# USB3_Replication.net
KiCad netlist of a schematic drawn in Altium Designer
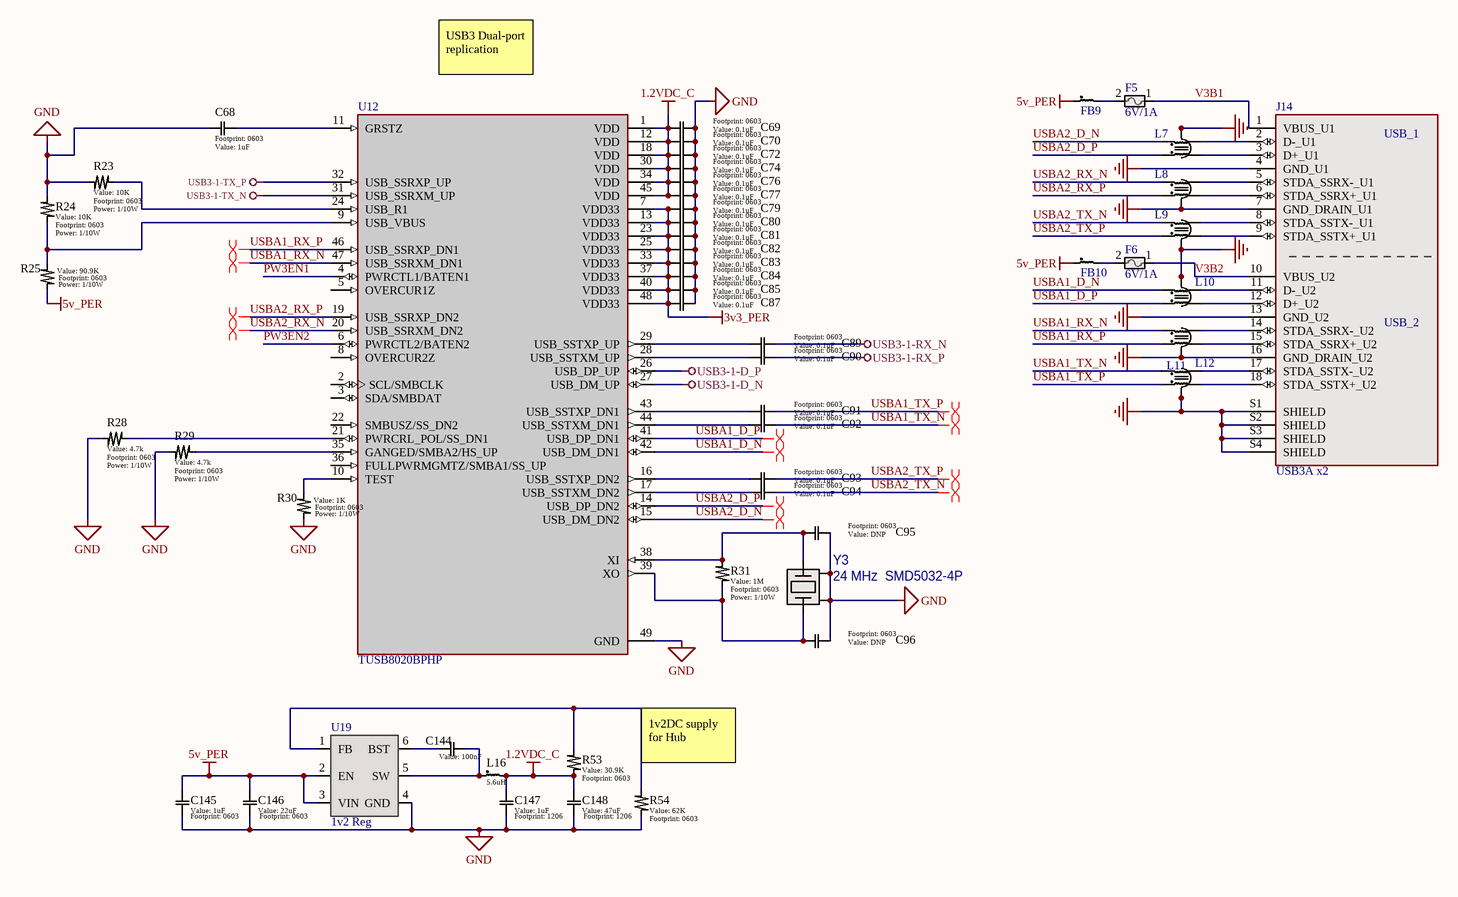
[diagram p0: USB3_Replication.SchDoc]

(export (version "E")
  (design (tool "Eeschema 10.0.6"))
  (components
    (comp (ref "C68")
      (value "1uF")
      (footprint "0603")
      (fields
        (field (name "VOLTAGE") ">10V")
        (field (name "TOLERANCE") "10%")
        (field (name "Comment") "Generic Capacitor")
      )
      (libsource (lib "Capacitors") (part "Generic Capacitor"))
    )
    (comp (ref "C69")
      (value "0.1uF")
      (footprint "0603")
      (fields
        (field (name "VOLTAGE") "10V")
        (field (name "TOLERANCE") "10%")
        (field (name "Comment") "Generic Capacitor")
      )
      (libsource (lib "Capacitors") (part "Generic Capacitor"))
    )
    (comp (ref "C70")
      (value "0.1uF")
      (footprint "0603")
      (fields
        (field (name "VOLTAGE") "10V")
        (field (name "TOLERANCE") "10%")
        (field (name "Comment") "Generic Capacitor")
      )
      (libsource (lib "Capacitors") (part "Generic Capacitor"))
    )
    (comp (ref "C72")
      (value "0.1uF")
      (footprint "0603")
      (fields
        (field (name "VOLTAGE") "10V")
        (field (name "TOLERANCE") "10%")
        (field (name "Comment") "Generic Capacitor")
      )
      (libsource (lib "Capacitors") (part "Generic Capacitor"))
    )
    (comp (ref "C74")
      (value "0.1uF")
      (footprint "0603")
      (fields
        (field (name "VOLTAGE") "10V")
        (field (name "TOLERANCE") "10%")
        (field (name "Comment") "Generic Capacitor")
      )
      (libsource (lib "Capacitors") (part "Generic Capacitor"))
    )
    (comp (ref "C76")
      (value "0.1uF")
      (footprint "0603")
      (fields
        (field (name "VOLTAGE") "10V")
        (field (name "TOLERANCE") "10%")
        (field (name "Comment") "Generic Capacitor")
      )
      (libsource (lib "Capacitors") (part "Generic Capacitor"))
    )
    (comp (ref "C77")
      (value "0.1uF")
      (footprint "0603")
      (fields
        (field (name "VOLTAGE") "10V")
        (field (name "TOLERANCE") "10%")
        (field (name "Comment") "Generic Capacitor")
      )
      (libsource (lib "Capacitors") (part "Generic Capacitor"))
    )
    (comp (ref "C79")
      (value "0.1uF")
      (footprint "0603")
      (fields
        (field (name "VOLTAGE") "10V")
        (field (name "TOLERANCE") "10%")
        (field (name "Comment") "Generic Capacitor")
      )
      (libsource (lib "Capacitors") (part "Generic Capacitor"))
    )
    (comp (ref "C80")
      (value "0.1uF")
      (footprint "0603")
      (fields
        (field (name "VOLTAGE") "10V")
        (field (name "TOLERANCE") "10%")
        (field (name "Comment") "Generic Capacitor")
      )
      (libsource (lib "Capacitors") (part "Generic Capacitor"))
    )
    (comp (ref "C81")
      (value "0.1uF")
      (footprint "0603")
      (fields
        (field (name "VOLTAGE") "10V")
        (field (name "TOLERANCE") "10%")
        (field (name "Comment") "Generic Capacitor")
      )
      (libsource (lib "Capacitors") (part "Generic Capacitor"))
    )
    (comp (ref "C82")
      (value "0.1uF")
      (footprint "0603")
      (fields
        (field (name "VOLTAGE") "10V")
        (field (name "TOLERANCE") "10%")
        (field (name "Comment") "Generic Capacitor")
      )
      (libsource (lib "Capacitors") (part "Generic Capacitor"))
    )
    (comp (ref "C83")
      (value "0.1uF")
      (footprint "0603")
      (fields
        (field (name "VOLTAGE") "10V")
        (field (name "TOLERANCE") "10%")
        (field (name "Comment") "Generic Capacitor")
      )
      (libsource (lib "Capacitors") (part "Generic Capacitor"))
    )
    (comp (ref "C84")
      (value "0.1uF")
      (footprint "0603")
      (fields
        (field (name "VOLTAGE") "10V")
        (field (name "TOLERANCE") "10%")
        (field (name "Comment") "Generic Capacitor")
      )
      (libsource (lib "Capacitors") (part "Generic Capacitor"))
    )
    (comp (ref "C85")
      (value "0.1uF")
      (footprint "0603")
      (fields
        (field (name "VOLTAGE") "10V")
        (field (name "TOLERANCE") "10%")
        (field (name "Comment") "Generic Capacitor")
      )
      (libsource (lib "Capacitors") (part "Generic Capacitor"))
    )
    (comp (ref "C87")
      (value "0.1uF")
      (footprint "0603")
      (fields
        (field (name "VOLTAGE") "10V")
        (field (name "TOLERANCE") "10%")
        (field (name "Comment") "Generic Capacitor")
      )
      (libsource (lib "Capacitors") (part "Generic Capacitor"))
    )
    (comp (ref "C89")
      (value "0.1uF")
      (footprint "0603")
      (fields
        (field (name "VOLTAGE") "10V")
        (field (name "TOLERANCE") "10%")
        (field (name "Comment") "Generic Capacitor")
      )
      (libsource (lib "Capacitors") (part "Generic Capacitor"))
    )
    (comp (ref "C90")
      (value "0.1uF")
      (footprint "0603")
      (fields
        (field (name "VOLTAGE") "10V")
        (field (name "TOLERANCE") "10%")
        (field (name "Comment") "Generic Capacitor")
      )
      (libsource (lib "Capacitors") (part "Generic Capacitor"))
    )
    (comp (ref "C91")
      (value "0.1uF")
      (footprint "0603")
      (fields
        (field (name "VOLTAGE") "10V")
        (field (name "TOLERANCE") "10%")
        (field (name "Comment") "Generic Capacitor")
      )
      (libsource (lib "Capacitors") (part "Generic Capacitor"))
    )
    (comp (ref "C92")
      (value "0.1uF")
      (footprint "0603")
      (fields
        (field (name "VOLTAGE") "10V")
        (field (name "TOLERANCE") "10%")
        (field (name "Comment") "Generic Capacitor")
      )
      (libsource (lib "Capacitors") (part "Generic Capacitor"))
    )
    (comp (ref "C93")
      (value "0.1uF")
      (footprint "0603")
      (fields
        (field (name "VOLTAGE") "10V")
        (field (name "TOLERANCE") "10%")
        (field (name "Comment") "Generic Capacitor")
      )
      (libsource (lib "Capacitors") (part "Generic Capacitor"))
    )
    (comp (ref "C94")
      (value "0.1uF")
      (footprint "0603")
      (fields
        (field (name "VOLTAGE") "10V")
        (field (name "TOLERANCE") "10%")
        (field (name "Comment") "Generic Capacitor")
      )
      (libsource (lib "Capacitors") (part "Generic Capacitor"))
    )
    (comp (ref "C95")
      (value "DNP")
      (footprint "0603")
      (fields
        (field (name "VOLTAGE") ">10V")
        (field (name "TOLERANCE") "10%")
        (field (name "Comment") "Generic Capacitor")
      )
      (libsource (lib "Capacitors") (part "Generic Capacitor"))
    )
    (comp (ref "C96")
      (value "DNP")
      (footprint "0603")
      (fields
        (field (name "VOLTAGE") ">10V")
        (field (name "TOLERANCE") "10%")
        (field (name "Comment") "Generic Capacitor")
      )
      (libsource (lib "Capacitors") (part "Generic Capacitor"))
    )
    (comp (ref "C144")
      (value "100nF")
      (footprint "0603")
      (fields
        (field (name "VOLTAGE") ">10V")
        (field (name "TOLERANCE") "10%")
        (field (name "Comment") "Generic Capacitor")
      )
      (libsource (lib "Capacitors") (part "Generic Capacitor"))
    )
    (comp (ref "C145")
      (value "1uF")
      (footprint "0603")
      (fields
        (field (name "VOLTAGE") ">10V")
        (field (name "TOLERANCE") "10%")
        (field (name "Comment") "Generic Capacitor")
      )
      (libsource (lib "Capacitors") (part "Generic Capacitor"))
    )
    (comp (ref "C146")
      (value "22uF")
      (footprint "0603")
      (fields
        (field (name "VOLTAGE") ">10V")
        (field (name "TOLERANCE") "10%")
        (field (name "Comment") "Generic Capacitor")
      )
      (libsource (lib "Capacitors") (part "Generic Capacitor"))
    )
    (comp (ref "C147")
      (value "1uF")
      (footprint "1206")
      (fields
        (field (name "VOLTAGE") ">10V")
        (field (name "TOLERANCE") "10%")
        (field (name "Comment") "Generic Capacitor")
      )
      (libsource (lib "Capacitors") (part "Generic Capacitor"))
    )
    (comp (ref "C148")
      (value "47uF")
      (footprint "1206")
      (fields
        (field (name "VOLTAGE") ">10V")
        (field (name "TOLERANCE") "10%")
        (field (name "Comment") "Generic Capacitor")
      )
      (libsource (lib "Capacitors") (part "Generic Capacitor"))
    )
    (comp (ref "F5")
      (value "6V/1A")
      (footprint "0805")
      (description "Polymeric PTC Resettable Fuse 6V 1 A Ih Surface Mount 0805 (2012 Metric), Concave")
      (fields (field (name "MANUFACTURER") "Bel") (field (name "MANUFACTURER PART NUMBER") "0ZCK0100FF2E"))
      (libsource (lib "Regulators") (part "0ZCK0100FF2E"))
    )
    (comp (ref "F6")
      (value "6V/1A")
      (footprint "0805")
      (description "Polymeric PTC Resettable Fuse 6V 1 A Ih Surface Mount 0805 (2012 Metric), Concave")
      (fields (field (name "MANUFACTURER") "Bel") (field (name "MANUFACTURER PART NUMBER") "0ZCK0100FF2E"))
      (libsource (lib "Regulators") (part "0ZCK0100FF2E"))
    )
    (comp (ref "FB9")
      (value "0603 Ferrite")
      (footprint "0603")
      (description "120 Ohms @ 100 MHz 1 Signal Line Ferrite Bead 0603 (1608 Metric) 500mA 180mOhm")
      (fields
        (field (name "MANUFACTURER") "Pulse")
        (field (name "MANUFACTURER PART NUMBER") "PE-0603FB121ST")
      )
      (libsource (lib "Inductors") (part "PE-0603FB121ST"))
    )
    (comp (ref "FB10")
      (value "0603 Ferrite")
      (footprint "0603")
      (description "120 Ohms @ 100 MHz 1 Signal Line Ferrite Bead 0603 (1608 Metric) 500mA 180mOhm")
      (fields
        (field (name "MANUFACTURER") "Pulse")
        (field (name "MANUFACTURER PART NUMBER") "PE-0603FB121ST")
      )
      (libsource (lib "Inductors") (part "PE-0603FB121ST"))
    )
    (comp (ref "J14")
      (value "USB3A x2")
      (footprint "0484060003")
      (fields (field (name "MP") "0484060003") (field (name "MF") "Molex"))
      (libsource (lib "Connectors") (part "0484060003"))
    )
    (comp (ref "L7")
      (value "2CH CMC")
      (footprint "SMD-6-2CH")
      (description "35Ω@100MHz -40℃~+85℃ 4Ω 5V 2 100mA SMD Common Mode Filters ROHS")
      (libsource (lib "") (part "ICMEF112P350MFR_1"))
    )
    (comp (ref "L8")
      (value "2CH CMC")
      (footprint "SMD-6-2CH")
      (description "35Ω@100MHz -40℃~+85℃ 4Ω 5V 2 100mA SMD Common Mode Filters ROHS")
      (libsource (lib "Inductors") (part "ICMEF112P350MFR"))
    )
    (comp (ref "L9")
      (value "2CH CMC")
      (footprint "SMD-6-2CH")
      (description "35Ω@100MHz -40℃~+85℃ 4Ω 5V 2 100mA SMD Common Mode Filters ROHS")
      (libsource (lib "Inductors") (part "ICMEF112P350MFR"))
    )
    (comp (ref "L10")
      (value "2CH CMC")
      (footprint "SMD-6-2CH")
      (description "35Ω@100MHz -40℃~+85℃ 4Ω 5V 2 100mA SMD Common Mode Filters ROHS")
      (libsource (lib "") (part "ICMEF112P350MFR_1"))
    )
    (comp (ref "L11")
      (value "2CH CMC")
      (footprint "SMD-6-2CH")
      (description "35Ω@100MHz -40℃~+85℃ 4Ω 5V 2 100mA SMD Common Mode Filters ROHS")
      (libsource (lib "Inductors") (part "ICMEF112P350MFR"))
    )
    (comp (ref "L12")
      (value "2CH CMC")
      (footprint "SMD-6-2CH")
      (description "35Ω@100MHz -40℃~+85℃ 4Ω 5V 2 100mA SMD Common Mode Filters ROHS")
      (libsource (lib "Inductors") (part "ICMEF112P350MFR"))
    )
    (comp (ref "L16")
      (value "5.6uH")
      (footprint "TMPC0402HP")
      (description "2A 5.6uH ±20% SMD Power Inductor")
      (libsource (lib "Inductors") (part "TMPC0402HP-5R6MG-Z02"))
    )
    (comp (ref "R23")
      (value "10K")
      (footprint "0603")
      (fields
        (field (name "TOLERANCE") "1%")
        (field (name "POWER") "1/10W")
        (field (name "Comment") "Generic Resistor")
      )
      (libsource (lib "Resistors") (part "Generic Resistor"))
    )
    (comp (ref "R24")
      (value "10K")
      (footprint "0603")
      (fields
        (field (name "TOLERANCE") "1%")
        (field (name "POWER") "1/10W")
        (field (name "Comment") "Generic Resistor")
      )
      (libsource (lib "Resistors") (part "Generic Resistor"))
    )
    (comp (ref "R25")
      (value "90.9K")
      (footprint "0603")
      (fields
        (field (name "TOLERANCE") "1%")
        (field (name "POWER") "1/10W")
        (field (name "Comment") "Generic Resistor")
      )
      (libsource (lib "Resistors") (part "Generic Resistor"))
    )
    (comp (ref "R28")
      (value "4.7k")
      (footprint "0603")
      (fields
        (field (name "TOLERANCE") "1%")
        (field (name "POWER") "1/10W")
        (field (name "Comment") "Generic Resistor")
      )
      (libsource (lib "Resistors") (part "Generic Resistor"))
    )
    (comp (ref "R29")
      (value "4.7k")
      (footprint "0603")
      (fields
        (field (name "TOLERANCE") "1%")
        (field (name "POWER") "1/10W")
        (field (name "Comment") "Generic Resistor")
      )
      (libsource (lib "Resistors") (part "Generic Resistor"))
    )
    (comp (ref "R30")
      (value "1K")
      (footprint "0603")
      (fields
        (field (name "TOLERANCE") "1%")
        (field (name "POWER") "1/10W")
        (field (name "Comment") "Generic Resistor")
      )
      (libsource (lib "Resistors") (part "Generic Resistor"))
    )
    (comp (ref "R31")
      (value "1M")
      (footprint "0603")
      (fields
        (field (name "TOLERANCE") "1%")
        (field (name "POWER") "1/10W")
        (field (name "Comment") "Generic Resistor")
      )
      (libsource (lib "Resistors") (part "Generic Resistor"))
    )
    (comp (ref "R53")
      (value "30.9K")
      (footprint "0603")
      (fields
        (field (name "TOLERANCE") "1%")
        (field (name "POWER") "1/10W")
        (field (name "Comment") "Generic Resistor")
      )
      (libsource (lib "Resistors") (part "Generic Resistor"))
    )
    (comp (ref "R54")
      (value "62K")
      (footprint "0603")
      (fields
        (field (name "TOLERANCE") "1%")
        (field (name "POWER") "1/10W")
        (field (name "Comment") "Generic Resistor")
      )
      (libsource (lib "Resistors") (part "Generic Resistor"))
    )
    (comp (ref "U12")
      (value "TUSB8020BPHP")
      (footprint "HTQFP-48(7x7)")
      (description "USB Hub Controller USB 3.0")
      (libsource (lib "Misc ICs") (part "TUSB8020BPHP"))
    )
    (comp (ref "U19")
      (value "1v2 Reg")
      (footprint "TSOT-23-6")
      (description "Step-down type Adjustable 2A 1.2V~12V 3.8V~32V TSOT-23-6 DC-DC Converter")
      (libsource (lib "Regulators") (part "AP63201WU-7"))
    )
    (comp (ref "Y3")
      (value "24 MHz  SMD5032-4P")
      (footprint "ECS-240-18-30BQ-DS")
      (description "24 MHz ±30ppm Crystal 18pF 30 Ohms 4-SMD, No Lead")
      (libsource (lib "Gamber - Johnson LLC") (part "ECS-240-18-30BQ-DS"))
    )
  )
  (nets
    (net (code "1") (name "/PW3EN1") (class "Default")
      (node (ref "U12") (pin "4") (pinfunction "PWRCTL1/BATEN1_4") (pintype "bidirectional"))
    )
    (net (code "2") (name "/PW3EN2") (class "Default")
      (node (ref "U12") (pin "6") (pinfunction "PWRCTL2/BATEN2_6") (pintype "bidirectional"))
    )
    (net (code "3") (name "/USBA1_D_N") (class "Default")
      (node (ref "L10") (pin "2") (pinfunction "2_2") (pintype "passive"))
      (node (ref "U12") (pin "42") (pinfunction "USB_DM_DN1_42") (pintype "bidirectional"))
    )
    (net (code "4") (name "/USBA1_D_P") (class "Default")
      (node (ref "L10") (pin "1") (pinfunction "1_1") (pintype "passive"))
      (node (ref "U12") (pin "41") (pinfunction "USB_DP_DN1_41") (pintype "bidirectional"))
    )
    (net (code "5") (name "/USBA1_RX_N") (class "Default")
      (node (ref "L11") (pin "1") (pinfunction "1_1") (pintype "passive"))
      (node (ref "U12") (pin "47") (pinfunction "USB_SSRXM_DN1_47") (pintype "input"))
    )
    (net (code "6") (name "/USBA1_RX_P") (class "Default")
      (node (ref "L11") (pin "2") (pinfunction "2_2") (pintype "passive"))
      (node (ref "U12") (pin "46") (pinfunction "USB_SSRXP_DN1_46") (pintype "input"))
    )
    (net (code "7") (name "/USBA1_TX_N") (class "Default")
      (node (ref "C92") (pin "1") (pinfunction "1_1") (pintype "passive"))
      (node (ref "L12") (pin "1") (pinfunction "1_1") (pintype "passive"))
    )
    (net (code "8") (name "/USBA1_TX_P") (class "Default")
      (node (ref "C91") (pin "1") (pinfunction "1_1") (pintype "passive"))
      (node (ref "L12") (pin "2") (pinfunction "2_2") (pintype "passive"))
    )
    (net (code "9") (name "/USBA2_D_N") (class "Default")
      (node (ref "L7") (pin "2") (pinfunction "2_2") (pintype "passive"))
      (node (ref "U12") (pin "15") (pinfunction "USB_DM_DN2_15") (pintype "bidirectional"))
    )
    (net (code "10") (name "/USBA2_D_P") (class "Default")
      (node (ref "L7") (pin "1") (pinfunction "1_1") (pintype "passive"))
      (node (ref "U12") (pin "14") (pinfunction "USB_DP_DN2_14") (pintype "bidirectional"))
    )
    (net (code "11") (name "/USBA2_RX_N") (class "Default")
      (node (ref "L8") (pin "1") (pinfunction "1_1") (pintype "passive"))
      (node (ref "U12") (pin "20") (pinfunction "USB_SSRXM_DN2_20") (pintype "input"))
    )
    (net (code "12") (name "/USBA2_RX_P") (class "Default")
      (node (ref "L8") (pin "2") (pinfunction "2_2") (pintype "passive"))
      (node (ref "U12") (pin "19") (pinfunction "USB_SSRXP_DN2_19") (pintype "input"))
    )
    (net (code "13") (name "/USBA2_TX_N") (class "Default")
      (node (ref "C94") (pin "1") (pinfunction "1_1") (pintype "passive"))
      (node (ref "L9") (pin "1") (pinfunction "1_1") (pintype "passive"))
    )
    (net (code "14") (name "/USBA2_TX_P") (class "Default")
      (node (ref "C93") (pin "1") (pinfunction "1_1") (pintype "passive"))
      (node (ref "L9") (pin "2") (pinfunction "2_2") (pintype "passive"))
    )
    (net (code "15") (name "/V3B1") (class "Default")
      (node (ref "F5") (pin "1") (pinfunction "1_1") (pintype "passive"))
      (node (ref "J14") (pin "1") (pinfunction "VBUS_U1_1") (pintype "power_in"))
    )
    (net (code "16") (name "/V3B2") (class "Default")
      (node (ref "F6") (pin "1") (pinfunction "1_1") (pintype "passive"))
      (node (ref "J14") (pin "10") (pinfunction "VBUS_U2_10") (pintype "power_in"))
    )
    (net (code "17") (name "1.2VDC_C") (class "Default")
      (node (ref "C147") (pin "1") (pinfunction "1_1") (pintype "passive"))
      (node (ref "C148") (pin "1") (pinfunction "1_1") (pintype "passive"))
      (node (ref "C69") (pin "2") (pinfunction "2_2") (pintype "passive"))
      (node (ref "C70") (pin "2") (pinfunction "2_2") (pintype "passive"))
      (node (ref "C72") (pin "2") (pinfunction "2_2") (pintype "passive"))
      (node (ref "C74") (pin "2") (pinfunction "2_2") (pintype "passive"))
      (node (ref "C76") (pin "2") (pinfunction "2_2") (pintype "passive"))
      (node (ref "C77") (pin "2") (pinfunction "2_2") (pintype "passive"))
      (node (ref "L16") (pin "2") (pinfunction "2_2") (pintype "passive"))
      (node (ref "R53") (pin "1") (pinfunction "1_1") (pintype "passive"))
      (node (ref "U12") (pin "1") (pinfunction "VDD_1") (pintype "power_in"))
      (node (ref "U12") (pin "12") (pinfunction "VDD_12") (pintype "power_in"))
      (node (ref "U12") (pin "18") (pinfunction "VDD_18") (pintype "power_in"))
      (node (ref "U12") (pin "30") (pinfunction "VDD_30") (pintype "power_in"))
      (node (ref "U12") (pin "34") (pinfunction "VDD_34") (pintype "power_in"))
      (node (ref "U12") (pin "45") (pinfunction "VDD_45") (pintype "power_in"))
    )
    (net (code "18") (name "3v3_PER") (class "Default")
      (node (ref "C79") (pin "2") (pinfunction "2_2") (pintype "passive"))
      (node (ref "C80") (pin "2") (pinfunction "2_2") (pintype "passive"))
      (node (ref "C81") (pin "2") (pinfunction "2_2") (pintype "passive"))
      (node (ref "C82") (pin "2") (pinfunction "2_2") (pintype "passive"))
      (node (ref "C83") (pin "2") (pinfunction "2_2") (pintype "passive"))
      (node (ref "C84") (pin "2") (pinfunction "2_2") (pintype "passive"))
      (node (ref "C85") (pin "2") (pinfunction "2_2") (pintype "passive"))
      (node (ref "C87") (pin "2") (pinfunction "2_2") (pintype "passive"))
      (node (ref "U12") (pin "13") (pinfunction "VDD33_13") (pintype "power_in"))
      (node (ref "U12") (pin "23") (pinfunction "VDD33_23") (pintype "power_in"))
      (node (ref "U12") (pin "25") (pinfunction "VDD33_25") (pintype "power_in"))
      (node (ref "U12") (pin "33") (pinfunction "VDD33_33") (pintype "power_in"))
      (node (ref "U12") (pin "37") (pinfunction "VDD33_37") (pintype "power_in"))
      (node (ref "U12") (pin "40") (pinfunction "VDD33_40") (pintype "power_in"))
      (node (ref "U12") (pin "48") (pinfunction "VDD33_48") (pintype "power_in"))
      (node (ref "U12") (pin "7") (pinfunction "VDD33_7") (pintype "power_in"))
    )
    (net (code "19") (name "5v_PER") (class "Default")
      (node (ref "C145") (pin "1") (pinfunction "1_1") (pintype "passive"))
      (node (ref "C146") (pin "1") (pinfunction "1_1") (pintype "passive"))
      (node (ref "FB10") (pin "1") (pinfunction "1_1") (pintype "passive"))
      (node (ref "FB9") (pin "1") (pinfunction "1_1") (pintype "passive"))
      (node (ref "R25") (pin "1") (pinfunction "1_1") (pintype "passive"))
      (node (ref "U19") (pin "2") (pinfunction "EN_2") (pintype "passive"))
      (node (ref "U19") (pin "3") (pinfunction "VIN_3") (pintype "passive"))
    )
    (net (code "20") (name "GND") (class "Default")
      (node (ref "C145") (pin "2") (pinfunction "2_2") (pintype "passive"))
      (node (ref "C146") (pin "2") (pinfunction "2_2") (pintype "passive"))
      (node (ref "C147") (pin "2") (pinfunction "2_2") (pintype "passive"))
      (node (ref "C148") (pin "2") (pinfunction "2_2") (pintype "passive"))
      (node (ref "C68") (pin "1") (pinfunction "1_1") (pintype "passive"))
      (node (ref "C69") (pin "1") (pinfunction "1_1") (pintype "passive"))
      (node (ref "C70") (pin "1") (pinfunction "1_1") (pintype "passive"))
      (node (ref "C72") (pin "1") (pinfunction "1_1") (pintype "passive"))
      (node (ref "C74") (pin "1") (pinfunction "1_1") (pintype "passive"))
      (node (ref "C76") (pin "1") (pinfunction "1_1") (pintype "passive"))
      (node (ref "C77") (pin "1") (pinfunction "1_1") (pintype "passive"))
      (node (ref "C79") (pin "1") (pinfunction "1_1") (pintype "passive"))
      (node (ref "C80") (pin "1") (pinfunction "1_1") (pintype "passive"))
      (node (ref "C81") (pin "1") (pinfunction "1_1") (pintype "passive"))
      (node (ref "C82") (pin "1") (pinfunction "1_1") (pintype "passive"))
      (node (ref "C83") (pin "1") (pinfunction "1_1") (pintype "passive"))
      (node (ref "C84") (pin "1") (pinfunction "1_1") (pintype "passive"))
      (node (ref "C85") (pin "1") (pinfunction "1_1") (pintype "passive"))
      (node (ref "C87") (pin "1") (pinfunction "1_1") (pintype "passive"))
      (node (ref "C95") (pin "1") (pinfunction "1_1") (pintype "passive"))
      (node (ref "C96") (pin "1") (pinfunction "1_1") (pintype "passive"))
      (node (ref "J14") (pin "13") (pinfunction "GND_U2_13") (pintype "power_in"))
      (node (ref "J14") (pin "16") (pinfunction "GND_DRAIN_U2_16") (pintype "power_in"))
      (node (ref "J14") (pin "4") (pinfunction "GND_U1_4") (pintype "power_in"))
      (node (ref "J14") (pin "7") (pinfunction "GND_DRAIN_U1_7") (pintype "power_in"))
      (node (ref "J14") (pin "S1") (pinfunction "SHIELD_S1") (pintype "passive"))
      (node (ref "J14") (pin "S2") (pinfunction "SHIELD_S2") (pintype "passive"))
      (node (ref "J14") (pin "S3") (pinfunction "SHIELD_S3") (pintype "passive"))
      (node (ref "J14") (pin "S4") (pinfunction "SHIELD_S4") (pintype "passive"))
      (node (ref "L10") (pin "5") (pinfunction "5_5") (pintype "passive"))
      (node (ref "L10") (pin "6") (pinfunction "6_6") (pintype "passive"))
      (node (ref "L11") (pin "5") (pinfunction "5_5") (pintype "passive"))
      (node (ref "L11") (pin "6") (pinfunction "6_6") (pintype "passive"))
      (node (ref "L12") (pin "5") (pinfunction "5_5") (pintype "passive"))
      (node (ref "L12") (pin "6") (pinfunction "6_6") (pintype "passive"))
      (node (ref "L7") (pin "5") (pinfunction "5_5") (pintype "passive"))
      (node (ref "L7") (pin "6") (pinfunction "6_6") (pintype "passive"))
      (node (ref "L8") (pin "5") (pinfunction "5_5") (pintype "passive"))
      (node (ref "L8") (pin "6") (pinfunction "6_6") (pintype "passive"))
      (node (ref "L9") (pin "5") (pinfunction "5_5") (pintype "passive"))
      (node (ref "L9") (pin "6") (pinfunction "6_6") (pintype "passive"))
      (node (ref "R23") (pin "1") (pinfunction "1_1") (pintype "passive"))
      (node (ref "R24") (pin "1") (pinfunction "1_1") (pintype "passive"))
      (node (ref "R28") (pin "1") (pinfunction "1_1") (pintype "passive"))
      (node (ref "R29") (pin "1") (pinfunction "1_1") (pintype "passive"))
      (node (ref "R30") (pin "1") (pinfunction "1_1") (pintype "passive"))
      (node (ref "R54") (pin "1") (pinfunction "1_1") (pintype "passive"))
      (node (ref "U12") (pin "49") (pinfunction "GND_49") (pintype "power_in"))
      (node (ref "U19") (pin "4") (pinfunction "GND_4") (pintype "power_in"))
      (node (ref "Y3") (pin "2") (pinfunction "GND_2") (pintype "power_in"))
      (node (ref "Y3") (pin "4") (pinfunction "GND_4") (pintype "power_in"))
    )
    (net (code "21") (name "Net-(F5-Pad2)") (class "Default")
      (node (ref "F5") (pin "2") (pinfunction "2_2") (pintype "passive"))
      (node (ref "FB9") (pin "2") (pinfunction "2_2") (pintype "passive"))
    )
    (net (code "22") (name "Net-(F6-Pad2)") (class "Default")
      (node (ref "F6") (pin "2") (pinfunction "2_2") (pintype "passive"))
      (node (ref "FB10") (pin "2") (pinfunction "2_2") (pintype "passive"))
    )
    (net (code "23") (name "Net-(J14-D+_U1)") (class "Default")
      (node (ref "J14") (pin "3") (pinfunction "D+_U1_3") (pintype "bidirectional"))
      (node (ref "L7") (pin "4") (pinfunction "4_4") (pintype "passive"))
    )
    (net (code "24") (name "Net-(J14-D+_U2)") (class "Default")
      (node (ref "J14") (pin "12") (pinfunction "D+_U2_12") (pintype "bidirectional"))
      (node (ref "L10") (pin "4") (pinfunction "4_4") (pintype "passive"))
    )
    (net (code "25") (name "Net-(J14-D-_U1)") (class "Default")
      (node (ref "J14") (pin "2") (pinfunction "D-_U1_2") (pintype "bidirectional"))
      (node (ref "L7") (pin "3") (pinfunction "3_3") (pintype "passive"))
    )
    (net (code "26") (name "Net-(J14-D-_U2)") (class "Default")
      (node (ref "J14") (pin "11") (pinfunction "D-_U2_11") (pintype "bidirectional"))
      (node (ref "L10") (pin "3") (pinfunction "3_3") (pintype "passive"))
    )
    (net (code "27") (name "Net-(J14-STDA_SSRX+_U1)") (class "Default")
      (node (ref "J14") (pin "6") (pinfunction "STDA_SSRX+_U1_6") (pintype "bidirectional"))
      (node (ref "L8") (pin "3") (pinfunction "3_3") (pintype "passive"))
    )
    (net (code "28") (name "Net-(J14-STDA_SSRX+_U2)") (class "Default")
      (node (ref "J14") (pin "15") (pinfunction "STDA_SSRX+_U2_15") (pintype "bidirectional"))
      (node (ref "L11") (pin "3") (pinfunction "3_3") (pintype "passive"))
    )
    (net (code "29") (name "Net-(J14-STDA_SSRX-_U1)") (class "Default")
      (node (ref "J14") (pin "5") (pinfunction "STDA_SSRX-_U1_5") (pintype "bidirectional"))
      (node (ref "L8") (pin "4") (pinfunction "4_4") (pintype "passive"))
    )
    (net (code "30") (name "Net-(J14-STDA_SSRX-_U2)") (class "Default")
      (node (ref "J14") (pin "14") (pinfunction "STDA_SSRX-_U2_14") (pintype "bidirectional"))
      (node (ref "L11") (pin "4") (pinfunction "4_4") (pintype "passive"))
    )
    (net (code "31") (name "Net-(J14-STDA_SSTX+_U1)") (class "Default")
      (node (ref "J14") (pin "9") (pinfunction "STDA_SSTX+_U1_9") (pintype "bidirectional"))
      (node (ref "L9") (pin "3") (pinfunction "3_3") (pintype "passive"))
    )
    (net (code "32") (name "Net-(J14-STDA_SSTX+_U2)") (class "Default")
      (node (ref "J14") (pin "18") (pinfunction "STDA_SSTX+_U2_18") (pintype "bidirectional"))
      (node (ref "L12") (pin "3") (pinfunction "3_3") (pintype "passive"))
    )
    (net (code "33") (name "Net-(J14-STDA_SSTX-_U1)") (class "Default")
      (node (ref "J14") (pin "8") (pinfunction "STDA_SSTX-_U1_8") (pintype "bidirectional"))
      (node (ref "L9") (pin "4") (pinfunction "4_4") (pintype "passive"))
    )
    (net (code "34") (name "Net-(J14-STDA_SSTX-_U2)") (class "Default")
      (node (ref "J14") (pin "17") (pinfunction "STDA_SSTX-_U2_17") (pintype "bidirectional"))
      (node (ref "L12") (pin "4") (pinfunction "4_4") (pintype "passive"))
    )
    (net (code "35") (name "Net-(U12-GANGED{slash}SMBA2{slash}HS_UP)") (class "Default")
      (node (ref "R29") (pin "2") (pinfunction "2_2") (pintype "passive"))
      (node (ref "U12") (pin "35") (pinfunction "GANGED/SMBA2/HS_UP_35") (pintype "input"))
    )
    (net (code "36") (name "Net-(U12-GRSTZ)") (class "Default")
      (node (ref "C68") (pin "2") (pinfunction "2_2") (pintype "passive"))
      (node (ref "U12") (pin "11") (pinfunction "GRSTZ_11") (pintype "input"))
    )
    (net (code "37") (name "Net-(U12-PWRCRL_POL{slash}SS_DN1)") (class "Default")
      (node (ref "R28") (pin "2") (pinfunction "2_2") (pintype "passive"))
      (node (ref "U12") (pin "21") (pinfunction "PWRCRL_POL/SS_DN1_21") (pintype "bidirectional"))
    )
    (net (code "38") (name "Net-(U12-TEST)") (class "Default")
      (node (ref "R30") (pin "2") (pinfunction "2_2") (pintype "passive"))
      (node (ref "U12") (pin "10") (pinfunction "TEST_10") (pintype "input"))
    )
    (net (code "39") (name "Net-(U12-USB_R1)") (class "Default")
      (node (ref "R23") (pin "2") (pinfunction "2_2") (pintype "passive"))
      (node (ref "U12") (pin "24") (pinfunction "USB_R1_24") (pintype "input"))
    )
    (net (code "40") (name "Net-(U12-USB_SSTXM_DN1)") (class "Default")
      (node (ref "C92") (pin "2") (pinfunction "2_2") (pintype "passive"))
      (node (ref "U12") (pin "44") (pinfunction "USB_SSTXM_DN1_44") (pintype "output"))
    )
    (net (code "41") (name "Net-(U12-USB_SSTXM_DN2)") (class "Default")
      (node (ref "C94") (pin "2") (pinfunction "2_2") (pintype "passive"))
      (node (ref "U12") (pin "17") (pinfunction "USB_SSTXM_DN2_17") (pintype "output"))
    )
    (net (code "42") (name "Net-(U12-USB_SSTXM_UP)") (class "Default")
      (node (ref "C90") (pin "2") (pinfunction "2_2") (pintype "passive"))
      (node (ref "U12") (pin "28") (pinfunction "USB_SSTXM_UP_28") (pintype "output"))
    )
    (net (code "43") (name "Net-(U12-USB_SSTXP_DN1)") (class "Default")
      (node (ref "C91") (pin "2") (pinfunction "2_2") (pintype "passive"))
      (node (ref "U12") (pin "43") (pinfunction "USB_SSTXP_DN1_43") (pintype "output"))
    )
    (net (code "44") (name "Net-(U12-USB_SSTXP_DN2)") (class "Default")
      (node (ref "C93") (pin "2") (pinfunction "2_2") (pintype "passive"))
      (node (ref "U12") (pin "16") (pinfunction "USB_SSTXP_DN2_16") (pintype "output"))
    )
    (net (code "45") (name "Net-(U12-USB_SSTXP_UP)") (class "Default")
      (node (ref "C89") (pin "2") (pinfunction "2_2") (pintype "passive"))
      (node (ref "U12") (pin "29") (pinfunction "USB_SSTXP_UP_29") (pintype "output"))
    )
    (net (code "46") (name "Net-(U12-USB_VBUS)") (class "Default")
      (node (ref "R24") (pin "2") (pinfunction "2_2") (pintype "passive"))
      (node (ref "R25") (pin "2") (pinfunction "2_2") (pintype "passive"))
      (node (ref "U12") (pin "9") (pinfunction "USB_VBUS_9") (pintype "input"))
    )
    (net (code "47") (name "Net-(U12-XI)") (class "Default")
      (node (ref "C95") (pin "2") (pinfunction "2_2") (pintype "passive"))
      (node (ref "R31") (pin "1") (pinfunction "1_1") (pintype "passive"))
      (node (ref "U12") (pin "38") (pinfunction "XI_38") (pintype "input"))
      (node (ref "Y3") (pin "3") (pintype "passive"))
    )
    (net (code "48") (name "Net-(U12-XO)") (class "Default")
      (node (ref "C96") (pin "2") (pinfunction "2_2") (pintype "passive"))
      (node (ref "R31") (pin "2") (pinfunction "2_2") (pintype "passive"))
      (node (ref "U12") (pin "39") (pinfunction "XO_39") (pintype "output"))
      (node (ref "Y3") (pin "1") (pintype "passive"))
    )
    (net (code "49") (name "Net-(U19-BST)") (class "Default")
      (node (ref "C144") (pin "1") (pinfunction "1_1") (pintype "passive"))
      (node (ref "U19") (pin "6") (pinfunction "BST_6") (pintype "passive"))
    )
    (net (code "50") (name "Net-(U19-FB)") (class "Default")
      (node (ref "R53") (pin "2") (pinfunction "2_2") (pintype "passive"))
      (node (ref "R54") (pin "2") (pinfunction "2_2") (pintype "passive"))
      (node (ref "U19") (pin "1") (pinfunction "FB_1") (pintype "passive"))
    )
    (net (code "51") (name "Net-(U19-SW)") (class "Default")
      (node (ref "C144") (pin "2") (pinfunction "2_2") (pintype "passive"))
      (node (ref "L16") (pin "1") (pinfunction "1_1") (pintype "passive"))
      (node (ref "U19") (pin "5") (pinfunction "SW_5") (pintype "passive"))
    )
    (net (code "52") (name "USB3-1-D_N") (class "Default")
      (node (ref "U12") (pin "27") (pinfunction "USB_DM_UP_27") (pintype "bidirectional"))
    )
    (net (code "53") (name "USB3-1-D_P") (class "Default")
      (node (ref "U12") (pin "26") (pinfunction "USB_DP_UP_26") (pintype "bidirectional"))
    )
    (net (code "54") (name "USB3-1-RX_N") (class "Default")
      (node (ref "C89") (pin "1") (pinfunction "1_1") (pintype "passive"))
    )
    (net (code "55") (name "USB3-1-RX_P") (class "Default")
      (node (ref "C90") (pin "1") (pinfunction "1_1") (pintype "passive"))
    )
    (net (code "56") (name "USB3-1-TX_N") (class "Default")
      (node (ref "U12") (pin "31") (pinfunction "USB_SSRXM_UP_31") (pintype "input"))
    )
    (net (code "57") (name "USB3-1-TX_P") (class "Default")
      (node (ref "U12") (pin "32") (pinfunction "USB_SSRXP_UP_32") (pintype "input"))
    )
    (net (code "58") (name "unconnected-(U12-FULLPWRMGMTZ{slash}SMBA1{slash}SS_UP-Pad36)") (class "Default")
      (node (ref "U12") (pin "36") (pinfunction "FULLPWRMGMTZ/SMBA1/SS_UP_36") (pintype "input"))
    )
    (net (code "59") (name "unconnected-(U12-OVERCUR1Z-Pad5)") (class "Default")
      (node (ref "U12") (pin "5") (pinfunction "OVERCUR1Z_5") (pintype "input"))
    )
    (net (code "60") (name "unconnected-(U12-OVERCUR2Z-Pad8)") (class "Default")
      (node (ref "U12") (pin "8") (pinfunction "OVERCUR2Z_8") (pintype "input"))
    )
    (net (code "61") (name "unconnected-(U12-SCL{slash}SMBCLK-Pad2)") (class "Default")
      (node (ref "U12") (pin "2") (pinfunction "SCL/SMBCLK_2") (pintype "bidirectional"))
    )
    (net (code "62") (name "unconnected-(U12-SDA{slash}SMBDAT-Pad3)") (class "Default")
      (node (ref "U12") (pin "3") (pinfunction "SDA/SMBDAT_3") (pintype "bidirectional"))
    )
    (net (code "63") (name "unconnected-(U12-SMBUSZ{slash}SS_DN2-Pad22)") (class "Default")
      (node (ref "U12") (pin "22") (pinfunction "SMBUSZ/SS_DN2_22") (pintype "input"))
    )
  )
)
